# tapecleaner.net
KiCad netlist of a schematic drawn in EAGLE
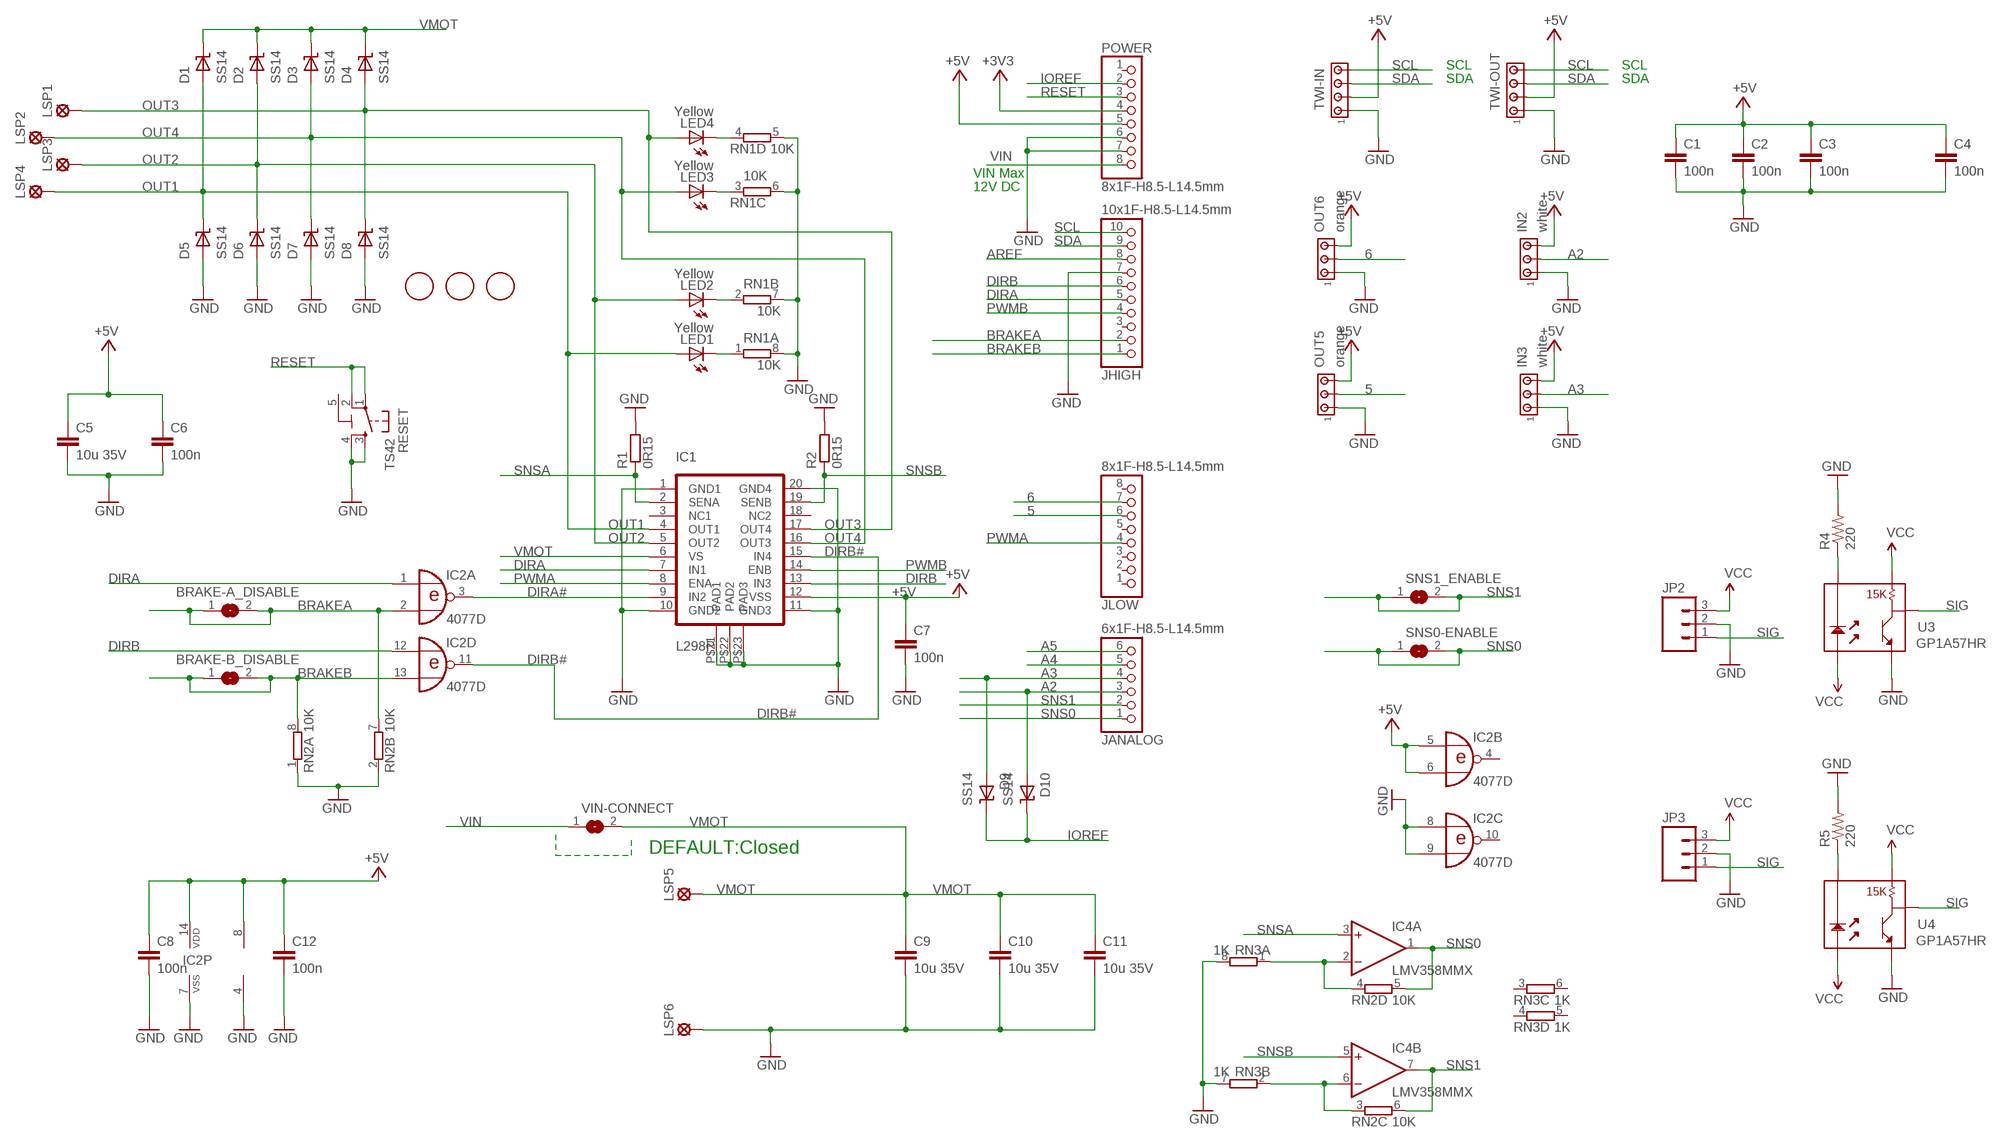
[diagram p0: schematic, sheet 1]
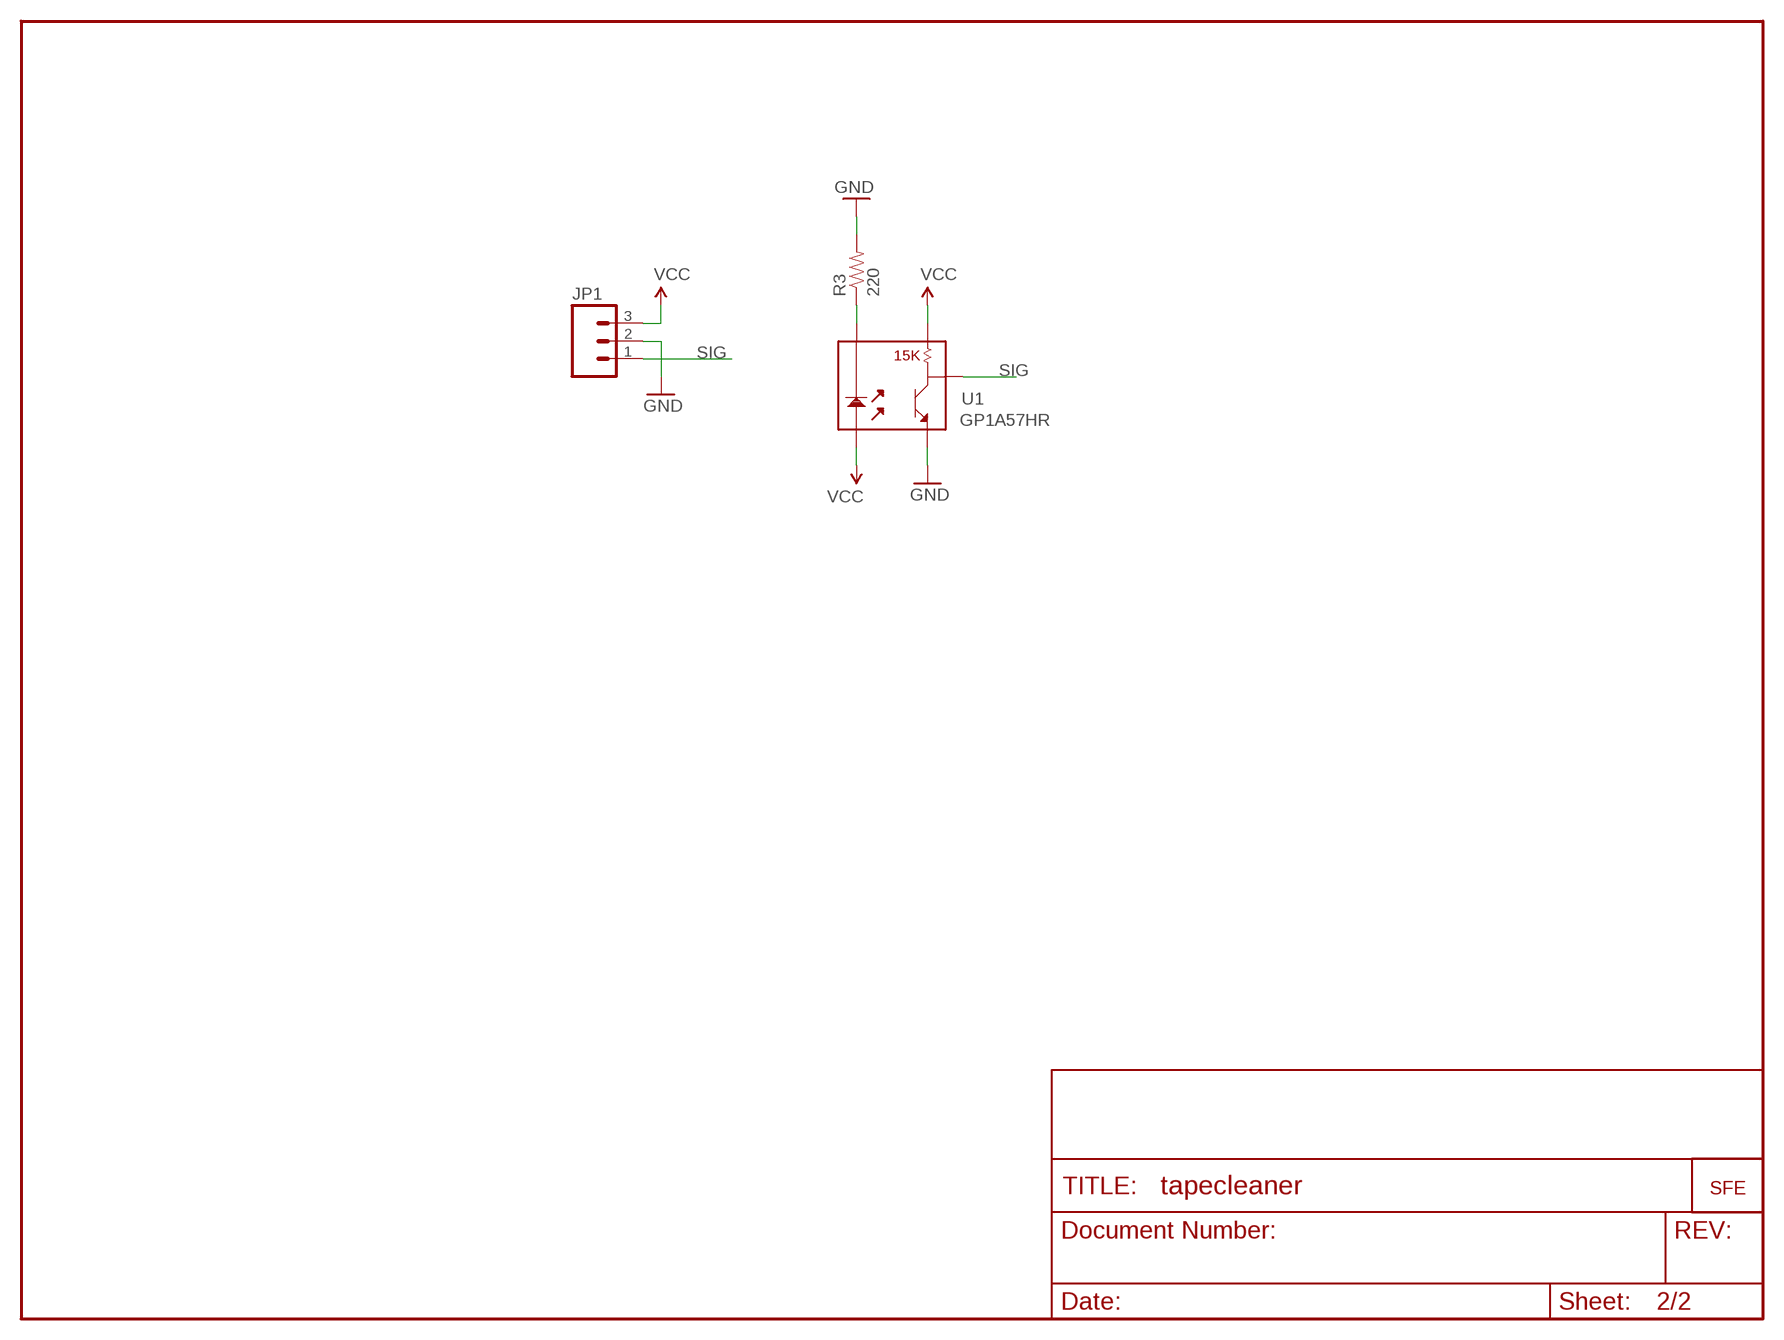
[diagram p1: schematic, sheet 2]

(export (version "E")
  (design (tool "Eeschema 10.0.6"))
  (components
    (comp (ref "JP1")
      (value "M03PTH")
      (footprint "eagle-import:1X03")
      (libsource (lib "eagle-import") (part "M03PTH"))
    )
    (comp (ref "R3")
      (value "220")
      (footprint "eagle-import:AXIAL-0.3")
      (libsource (lib "eagle-import") (part "RESISTORPTH1"))
    )
    (comp (ref "U1")
      (value "GP1A57HR")
      (footprint "eagle-import:GP1A57HR")
      (libsource (lib "eagle-import") (part "GP1A57HR"))
    )
    (comp (ref "U2")
      (value "LOGO-SFESK")
      (footprint "eagle-import:SFE-LOGO-FLAME")
      (libsource (lib "eagle-import") (part "LOGO-SFESK"))
    )
    (comp (ref "BRAKE-A_DISABLE")
      (value "SJ")
      (footprint "eagle-import:SJ")
      (libsource (lib "eagle-import") (part "SJ"))
    )
    (comp (ref "BRAKE-B_DISABLE")
      (value "SJ")
      (footprint "eagle-import:SJ")
      (libsource (lib "eagle-import") (part "SJ"))
    )
    (comp (ref "C1")
      (value "100n")
      (footprint "eagle-import:C0603-ROUND")
      (libsource (lib "eagle-import") (part "C-EUC0603"))
    )
    (comp (ref "C2")
      (value "100n")
      (footprint "eagle-import:C0603-ROUND")
      (libsource (lib "eagle-import") (part "C-EUC0603"))
    )
    (comp (ref "C3")
      (value "100n")
      (footprint "eagle-import:C0603-ROUND")
      (libsource (lib "eagle-import") (part "C-EUC0603"))
    )
    (comp (ref "C4")
      (value "100n")
      (footprint "eagle-import:C0603-ROUND")
      (libsource (lib "eagle-import") (part "C-EUC0603"))
    )
    (comp (ref "C5")
      (value "10u 35V")
      (footprint "eagle-import:C1210")
      (libsource (lib "eagle-import") (part "C-EUC1210"))
    )
    (comp (ref "C6")
      (value "100n")
      (footprint "eagle-import:C0603-ROUND")
      (libsource (lib "eagle-import") (part "C-EUC0603"))
    )
    (comp (ref "C7")
      (value "100n")
      (footprint "eagle-import:C0603-ROUND")
      (libsource (lib "eagle-import") (part "C-EUC0603"))
    )
    (comp (ref "C8")
      (value "100n")
      (footprint "eagle-import:C0603-ROUND")
      (libsource (lib "eagle-import") (part "C-EUC0603"))
    )
    (comp (ref "C9")
      (value "10u 35V")
      (footprint "eagle-import:C1210")
      (libsource (lib "eagle-import") (part "C-EUC1210"))
    )
    (comp (ref "C10")
      (value "10u 35V")
      (footprint "eagle-import:C1210")
      (libsource (lib "eagle-import") (part "C-EUC1210"))
    )
    (comp (ref "C11")
      (value "10u 35V")
      (footprint "eagle-import:C1210")
      (libsource (lib "eagle-import") (part "C-EUC1210"))
    )
    (comp (ref "C12")
      (value "100n")
      (footprint "eagle-import:C0603-ROUND")
      (libsource (lib "eagle-import") (part "C-EUC0603"))
    )
    (comp (ref "D1")
      (value "SS14")
      (footprint "eagle-import:SMA")
      (libsource (lib "eagle-import") (part "SS14"))
    )
    (comp (ref "D2")
      (value "SS14")
      (footprint "eagle-import:SMA")
      (libsource (lib "eagle-import") (part "SS14"))
    )
    (comp (ref "D3")
      (value "SS14")
      (footprint "eagle-import:SMA")
      (libsource (lib "eagle-import") (part "SS14"))
    )
    (comp (ref "D4")
      (value "SS14")
      (footprint "eagle-import:SMA")
      (libsource (lib "eagle-import") (part "SS14"))
    )
    (comp (ref "D5")
      (value "SS14")
      (footprint "eagle-import:SMA")
      (libsource (lib "eagle-import") (part "SS14"))
    )
    (comp (ref "D6")
      (value "SS14")
      (footprint "eagle-import:SMA")
      (libsource (lib "eagle-import") (part "SS14"))
    )
    (comp (ref "D7")
      (value "SS14")
      (footprint "eagle-import:SMA")
      (libsource (lib "eagle-import") (part "SS14"))
    )
    (comp (ref "D8")
      (value "SS14")
      (footprint "eagle-import:SMA")
      (libsource (lib "eagle-import") (part "SS14"))
    )
    (comp (ref "D9")
      (value "SS14")
      (footprint "eagle-import:SMA")
      (libsource (lib "eagle-import") (part "SS14"))
    )
    (comp (ref "D10")
      (value "SS14")
      (footprint "eagle-import:SMA")
      (libsource (lib "eagle-import") (part "SS14"))
    )
    (comp (ref "FID1")
      (value "FIDUCIALMOUNT")
      (footprint "eagle-import:FIDUCIA-MOUNT")
      (libsource (lib "eagle-import") (part "FIDUCIALMOUNT"))
    )
    (comp (ref "FID2")
      (value "FIDUCIALMOUNT")
      (footprint "eagle-import:FIDUCIA-MOUNT")
      (libsource (lib "eagle-import") (part "FIDUCIALMOUNT"))
    )
    (comp (ref "FID3")
      (value "FIDUCIALMOUNT")
      (footprint "eagle-import:FIDUCIA-MOUNT")
      (libsource (lib "eagle-import") (part "FIDUCIALMOUNT"))
    )
    (comp (ref "IC1")
      (value "L298P")
      (footprint "eagle-import:POWER-SO20")
      (libsource (lib "eagle-import") (part "L298P"))
    )
    (comp (ref "IC2")
      (value "4077D")
      (footprint "eagle-import:SO14")
      (libsource (lib "eagle-import") (part "4077D"))
    )
    (comp (ref "IC4")
      (value "LMV358MMX")
      (footprint "eagle-import:MSOP08")
      (libsource (lib "eagle-import") (part "LMV358?MMX"))
    )
    (comp (ref "IN2")
      (value "white")
      (footprint "eagle-import:10X03MTA")
      (libsource (lib "eagle-import") (part "MTA03-100"))
    )
    (comp (ref "IN3")
      (value "white")
      (footprint "eagle-import:10X03MTA")
      (libsource (lib "eagle-import") (part "MTA03-100"))
    )
    (comp (ref "JANALOG")
      (value "6x1F-H8.5-L14.5mm")
      (footprint "eagle-import:1X06-TH")
      (libsource (lib "eagle-import") (part "PINHD-1X6TH"))
    )
    (comp (ref "JHIGH")
      (value "10x1F-H8.5-L14.5mm")
      (footprint "eagle-import:1X10-TH")
      (libsource (lib "eagle-import") (part "PINHD-1X10TH"))
    )
    (comp (ref "JLOW")
      (value "8x1F-H8.5-L14.5mm")
      (footprint "eagle-import:1X08-TH")
      (libsource (lib "eagle-import") (part "PINHD-1X8TH"))
    )
    (comp (ref "JP2")
      (value "M03PTH")
      (footprint "eagle-import:1X03")
      (libsource (lib "eagle-import") (part "M03PTH"))
    )
    (comp (ref "JP3")
      (value "M03PTH")
      (footprint "eagle-import:1X03")
      (libsource (lib "eagle-import") (part "M03PTH"))
    )
    (comp (ref "LED1")
      (value "Yellow")
      (footprint "eagle-import:CHIPLED_0805")
      (libsource (lib "eagle-import") (part "LEDCHIPLED_0805"))
    )
    (comp (ref "LED2")
      (value "Yellow")
      (footprint "eagle-import:CHIPLED_0805")
      (libsource (lib "eagle-import") (part "LEDCHIPLED_0805"))
    )
    (comp (ref "LED3")
      (value "Yellow")
      (footprint "eagle-import:CHIPLED_0805")
      (libsource (lib "eagle-import") (part "LEDCHIPLED_0805"))
    )
    (comp (ref "LED4")
      (value "Yellow")
      (footprint "eagle-import:CHIPLED_0805")
      (libsource (lib "eagle-import") (part "LEDCHIPLED_0805"))
    )
    (comp (ref "LSP1")
      (value "LSP13")
      (footprint "eagle-import:LSP13")
      (libsource (lib "eagle-import") (part "LSP13"))
    )
    (comp (ref "LSP2")
      (value "LSP13")
      (footprint "eagle-import:LSP13")
      (libsource (lib "eagle-import") (part "LSP13"))
    )
    (comp (ref "LSP3")
      (value "LSP13")
      (footprint "eagle-import:LSP13")
      (libsource (lib "eagle-import") (part "LSP13"))
    )
    (comp (ref "LSP4")
      (value "LSP13")
      (footprint "eagle-import:LSP13")
      (libsource (lib "eagle-import") (part "LSP13"))
    )
    (comp (ref "LSP5")
      (value "LSP13")
      (footprint "eagle-import:LSP13")
      (libsource (lib "eagle-import") (part "LSP13"))
    )
    (comp (ref "LSP6")
      (value "LSP13")
      (footprint "eagle-import:LSP13")
      (libsource (lib "eagle-import") (part "LSP13"))
    )
    (comp (ref "OUT5")
      (value "orange")
      (footprint "eagle-import:10X03MTA")
      (libsource (lib "eagle-import") (part "MTA03-100"))
    )
    (comp (ref "OUT6")
      (value "orange")
      (footprint "eagle-import:10X03MTA")
      (libsource (lib "eagle-import") (part "MTA03-100"))
    )
    (comp (ref "POWER")
      (value "8x1F-H8.5-L14.5mm")
      (footprint "eagle-import:1X08-TH")
      (libsource (lib "eagle-import") (part "PINHD-1X8TH"))
    )
    (comp (ref "R1")
      (value "0R15")
      (footprint "eagle-import:R1206")
      (libsource (lib "eagle-import") (part "R-EU_R1206"))
    )
    (comp (ref "R2")
      (value "0R15")
      (footprint "eagle-import:R1206")
      (libsource (lib "eagle-import") (part "R-EU_R1206"))
    )
    (comp (ref "R4")
      (value "220")
      (footprint "eagle-import:AXIAL-0.3")
      (libsource (lib "eagle-import") (part "RESISTORPTH1"))
    )
    (comp (ref "R5")
      (value "220")
      (footprint "eagle-import:AXIAL-0.3")
      (libsource (lib "eagle-import") (part "RESISTORPTH1"))
    )
    (comp (ref "RESET")
      (value "TS42")
      (footprint "eagle-import:TS42")
      (libsource (lib "eagle-import") (part "TS42"))
    )
    (comp (ref "RN1")
      (value "10K")
      (footprint "eagle-import:CAY16")
      (libsource (lib "eagle-import") (part "4R-NCAY16"))
    )
    (comp (ref "RN2")
      (value "10K")
      (footprint "eagle-import:CAY16")
      (libsource (lib "eagle-import") (part "4R-NCAY16"))
    )
    (comp (ref "RN3")
      (value "1K")
      (footprint "eagle-import:CAY16")
      (libsource (lib "eagle-import") (part "4R-NCAY16"))
    )
    (comp (ref "SNS0-ENABLE")
      (value "SJ")
      (footprint "eagle-import:SJ")
      (libsource (lib "eagle-import") (part "SJ"))
    )
    (comp (ref "SNS1_ENABLE")
      (value "SJ")
      (footprint "eagle-import:SJ")
      (libsource (lib "eagle-import") (part "SJ"))
    )
    (comp (ref "TWI-IN")
      (value "MTA04-100")
      (footprint "eagle-import:10X04MTA")
      (libsource (lib "eagle-import") (part "MTA04-100"))
    )
    (comp (ref "TWI-OUT")
      (value "MTA04-100")
      (footprint "eagle-import:10X04MTA")
      (libsource (lib "eagle-import") (part "MTA04-100"))
    )
    (comp (ref "U3")
      (value "GP1A57HR")
      (footprint "eagle-import:GP1A57HR")
      (libsource (lib "eagle-import") (part "GP1A57HR"))
    )
    (comp (ref "U4")
      (value "GP1A57HR")
      (footprint "eagle-import:GP1A57HR")
      (libsource (lib "eagle-import") (part "GP1A57HR"))
    )
    (comp (ref "VIN-CONNECT")
      (value "SJ")
      (footprint "eagle-import:SJ")
      (libsource (lib "eagle-import") (part "SJ"))
    )
  )
  (nets
    (net (code "1") (name "+3V3") (class "Default")
      (node (ref "POWER") (pin "4") (pinfunction "4_4") (pintype "passive"))
    )
    (net (code "2") (name "+5V") (class "Default")
      (node (ref "C1") (pin "1") (pinfunction "1_1") (pintype "passive"))
      (node (ref "C12") (pin "1") (pinfunction "1_1") (pintype "passive"))
      (node (ref "C2") (pin "1") (pinfunction "1_1") (pintype "passive"))
      (node (ref "C3") (pin "1") (pinfunction "1_1") (pintype "passive"))
      (node (ref "C4") (pin "1") (pinfunction "1_1") (pintype "passive"))
      (node (ref "C5") (pin "1") (pinfunction "1_1") (pintype "passive"))
      (node (ref "C6") (pin "1") (pinfunction "1_1") (pintype "passive"))
      (node (ref "C7") (pin "1") (pinfunction "1_1") (pintype "passive"))
      (node (ref "C8") (pin "1") (pinfunction "1_1") (pintype "passive"))
      (node (ref "IC1") (pin "P$12") (pinfunction "VSS_P$12") (pintype "power_in"))
      (node (ref "IC2") (pin "14") (pinfunction "VDD_14") (pintype "power_in"))
      (node (ref "IC2") (pin "5") (pinfunction "I0_5") (pintype "input"))
      (node (ref "IC2") (pin "6") (pinfunction "I1_6") (pintype "input"))
      (node (ref "IC4") (pin "8") (pinfunction "V+_8") (pintype "power_in"))
      (node (ref "IN2") (pin "3") (pinfunction "3_3") (pintype "passive"))
      (node (ref "IN3") (pin "3") (pinfunction "3_3") (pintype "passive"))
      (node (ref "OUT5") (pin "3") (pinfunction "3_3") (pintype "passive"))
      (node (ref "OUT6") (pin "3") (pinfunction "3_3") (pintype "passive"))
      (node (ref "POWER") (pin "5") (pinfunction "5_5") (pintype "passive"))
      (node (ref "TWI-IN") (pin "2") (pinfunction "2_2") (pintype "passive"))
      (node (ref "TWI-OUT") (pin "2") (pinfunction "2_2") (pintype "passive"))
    )
    (net (code "3") (name "5") (class "Default")
      (node (ref "JLOW") (pin "6") (pinfunction "6_6") (pintype "passive"))
      (node (ref "OUT5") (pin "2") (pinfunction "2_2") (pintype "passive"))
    )
    (net (code "4") (name "5-GND") (class "Default")
      (node (ref "RESET") (pin "5") (pinfunction "5-GND_5") (pintype "power_in"))
    )
    (net (code "5") (name "6") (class "Default")
      (node (ref "JLOW") (pin "7") (pinfunction "7_7") (pintype "passive"))
      (node (ref "OUT6") (pin "2") (pinfunction "2_2") (pintype "passive"))
    )
    (net (code "6") (name "A2") (class "Default")
      (node (ref "D10") (pin "P$2") (pinfunction "A_P$2") (pintype "bidirectional"))
      (node (ref "IN2") (pin "2") (pinfunction "2_2") (pintype "passive"))
      (node (ref "JANALOG") (pin "3") (pinfunction "3_3") (pintype "passive"))
    )
    (net (code "7") (name "A3") (class "Default")
      (node (ref "D9") (pin "P$2") (pinfunction "A_P$2") (pintype "bidirectional"))
      (node (ref "IN3") (pin "2") (pinfunction "2_2") (pintype "passive"))
      (node (ref "JANALOG") (pin "4") (pinfunction "4_4") (pintype "passive"))
    )
    (net (code "8") (name "A4") (class "Default")
      (node (ref "JANALOG") (pin "5") (pinfunction "5_5") (pintype "passive"))
    )
    (net (code "9") (name "A5") (class "Default")
      (node (ref "JANALOG") (pin "6") (pinfunction "6_6") (pintype "passive"))
    )
    (net (code "10") (name "AREF") (class "Default")
      (node (ref "JHIGH") (pin "8") (pinfunction "8_8") (pintype "passive"))
    )
    (net (code "11") (name "BRAKEA") (class "Default")
      (node (ref "BRAKE-A_DISABLE") (pin "1") (pinfunction "1_1") (pintype "passive"))
      (node (ref "BRAKE-A_DISABLE") (pin "2") (pinfunction "2_2") (pintype "passive"))
      (node (ref "IC2") (pin "2") (pinfunction "I1_2") (pintype "input"))
      (node (ref "JHIGH") (pin "2") (pinfunction "2_2") (pintype "passive"))
      (node (ref "RN2") (pin "7") (pinfunction "2_7") (pintype "passive"))
    )
    (net (code "12") (name "BRAKEB") (class "Default")
      (node (ref "BRAKE-B_DISABLE") (pin "1") (pinfunction "1_1") (pintype "passive"))
      (node (ref "BRAKE-B_DISABLE") (pin "2") (pinfunction "2_2") (pintype "passive"))
      (node (ref "IC2") (pin "13") (pinfunction "I1_13") (pintype "input"))
      (node (ref "JHIGH") (pin "1") (pinfunction "1_1") (pintype "passive"))
      (node (ref "RN2") (pin "8") (pinfunction "2_8") (pintype "passive"))
    )
    (net (code "13") (name "DIRA") (class "Default")
      (node (ref "IC1") (pin "P$7") (pinfunction "IN1_P$7") (pintype "input"))
      (node (ref "IC2") (pin "1") (pinfunction "I0_1") (pintype "input"))
      (node (ref "JHIGH") (pin "5") (pinfunction "5_5") (pintype "passive"))
    )
    (net (code "14") (name "DIRA#") (class "Default")
      (node (ref "IC1") (pin "P$9") (pinfunction "IN2_P$9") (pintype "input"))
      (node (ref "IC2") (pin "3") (pinfunction "O_3") (pintype "output"))
    )
    (net (code "15") (name "DIRB") (class "Default")
      (node (ref "IC1") (pin "P$13") (pinfunction "IN3_P$13") (pintype "input"))
      (node (ref "IC2") (pin "12") (pinfunction "I0_12") (pintype "input"))
      (node (ref "JHIGH") (pin "6") (pinfunction "6_6") (pintype "passive"))
    )
    (net (code "16") (name "DIRB#") (class "Default")
      (node (ref "IC1") (pin "P$15") (pinfunction "IN4_P$15") (pintype "input"))
      (node (ref "IC2") (pin "11") (pinfunction "O_11") (pintype "output"))
    )
    (net (code "17") (name "GND") (class "Default")
      (node (ref "C1") (pin "2") (pinfunction "2_2") (pintype "passive"))
      (node (ref "C10") (pin "2") (pinfunction "2_2") (pintype "passive"))
      (node (ref "C11") (pin "2") (pinfunction "2_2") (pintype "passive"))
      (node (ref "C12") (pin "2") (pinfunction "2_2") (pintype "passive"))
      (node (ref "C2") (pin "2") (pinfunction "2_2") (pintype "passive"))
      (node (ref "C3") (pin "2") (pinfunction "2_2") (pintype "passive"))
      (node (ref "C4") (pin "2") (pinfunction "2_2") (pintype "passive"))
      (node (ref "C5") (pin "2") (pinfunction "2_2") (pintype "passive"))
      (node (ref "C6") (pin "2") (pinfunction "2_2") (pintype "passive"))
      (node (ref "C7") (pin "2") (pinfunction "2_2") (pintype "passive"))
      (node (ref "C8") (pin "2") (pinfunction "2_2") (pintype "passive"))
      (node (ref "C9") (pin "2") (pinfunction "2_2") (pintype "passive"))
      (node (ref "D5") (pin "P$2") (pinfunction "A_P$2") (pintype "bidirectional"))
      (node (ref "D6") (pin "P$2") (pinfunction "A_P$2") (pintype "bidirectional"))
      (node (ref "D7") (pin "P$2") (pinfunction "A_P$2") (pintype "bidirectional"))
      (node (ref "D8") (pin "P$2") (pinfunction "A_P$2") (pintype "bidirectional"))
      (node (ref "IC1") (pin "P$1") (pinfunction "GND1_P$1") (pintype "power_in"))
      (node (ref "IC1") (pin "P$10") (pinfunction "GND2_P$10") (pintype "power_in"))
      (node (ref "IC1") (pin "P$11") (pinfunction "GND3_P$11") (pintype "power_in"))
      (node (ref "IC1") (pin "P$20") (pinfunction "GND4_P$20") (pintype "power_in"))
      (node (ref "IC1") (pin "P$21") (pinfunction "PAD1_P$21") (pintype "passive"))
      (node (ref "IC1") (pin "P$22") (pinfunction "PAD2_P$22") (pintype "passive"))
      (node (ref "IC1") (pin "P$23") (pinfunction "PAD3_P$23") (pintype "passive"))
      (node (ref "IC2") (pin "7") (pinfunction "VSS_7") (pintype "power_in"))
      (node (ref "IC2") (pin "8") (pinfunction "I0_8") (pintype "input"))
      (node (ref "IC2") (pin "9") (pinfunction "I1_9") (pintype "input"))
      (node (ref "IC4") (pin "4") (pinfunction "V-_4") (pintype "power_in"))
      (node (ref "IN2") (pin "1") (pinfunction "1_1") (pintype "passive"))
      (node (ref "IN3") (pin "1") (pinfunction "1_1") (pintype "passive"))
      (node (ref "JHIGH") (pin "7") (pinfunction "7_7") (pintype "passive"))
      (node (ref "JP1") (pin "2") (pinfunction "2_2") (pintype "passive"))
      (node (ref "JP2") (pin "2") (pinfunction "2_2") (pintype "passive"))
      (node (ref "JP3") (pin "2") (pinfunction "2_2") (pintype "passive"))
      (node (ref "LSP6") (pin "MP") (pinfunction "MP_MP") (pintype "passive"))
      (node (ref "OUT5") (pin "1") (pinfunction "1_1") (pintype "passive"))
      (node (ref "OUT6") (pin "1") (pinfunction "1_1") (pintype "passive"))
      (node (ref "POWER") (pin "6") (pinfunction "6_6") (pintype "passive"))
      (node (ref "POWER") (pin "7") (pinfunction "7_7") (pintype "passive"))
      (node (ref "R1") (pin "2") (pinfunction "2_2") (pintype "passive"))
      (node (ref "R2") (pin "2") (pinfunction "2_2") (pintype "passive"))
      (node (ref "R3") (pin "P$2") (pinfunction "2_P$2") (pintype "passive"))
      (node (ref "R4") (pin "P$2") (pinfunction "2_P$2") (pintype "passive"))
      (node (ref "R5") (pin "P$2") (pinfunction "2_P$2") (pintype "passive"))
      (node (ref "RESET") (pin "3") (pinfunction "3_3") (pintype "passive"))
      (node (ref "RESET") (pin "4") (pinfunction "4_4") (pintype "passive"))
      (node (ref "RN1") (pin "5") (pinfunction "2_5") (pintype "passive"))
      (node (ref "RN1") (pin "6") (pinfunction "2_6") (pintype "passive"))
      (node (ref "RN1") (pin "7") (pinfunction "2_7") (pintype "passive"))
      (node (ref "RN1") (pin "8") (pinfunction "2_8") (pintype "passive"))
      (node (ref "RN2") (pin "1") (pinfunction "1_1") (pintype "passive"))
      (node (ref "RN2") (pin "2") (pinfunction "1_2") (pintype "passive"))
      (node (ref "RN3") (pin "7") (pinfunction "2_7") (pintype "passive"))
      (node (ref "RN3") (pin "8") (pinfunction "2_8") (pintype "passive"))
      (node (ref "TWI-IN") (pin "1") (pinfunction "1_1") (pintype "passive"))
      (node (ref "TWI-OUT") (pin "1") (pinfunction "1_1") (pintype "passive"))
      (node (ref "U1") (pin "5") (pinfunction "5_5") (pintype "bidirectional"))
      (node (ref "U3") (pin "5") (pinfunction "5_5") (pintype "bidirectional"))
      (node (ref "U4") (pin "5") (pinfunction "5_5") (pintype "bidirectional"))
    )
    (net (code "18") (name "IOREF") (class "Default")
      (node (ref "D10") (pin "P$1") (pinfunction "K_P$1") (pintype "bidirectional"))
      (node (ref "D9") (pin "P$1") (pinfunction "K_P$1") (pintype "bidirectional"))
      (node (ref "POWER") (pin "2") (pinfunction "2_2") (pintype "passive"))
    )
    (net (code "19") (name "Net-(IC4A--IN)") (class "Default")
      (node (ref "IC4") (pin "2") (pinfunction "-IN_2") (pintype "input"))
      (node (ref "RN2") (pin "4") (pinfunction "1_4") (pintype "passive"))
      (node (ref "RN3") (pin "1") (pinfunction "1_1") (pintype "passive"))
    )
    (net (code "20") (name "Net-(IC4B--IN)") (class "Default")
      (node (ref "IC4") (pin "6") (pinfunction "-IN_6") (pintype "input"))
      (node (ref "RN2") (pin "3") (pinfunction "1_3") (pintype "passive"))
      (node (ref "RN3") (pin "2") (pinfunction "1_2") (pintype "passive"))
    )
    (net (code "21") (name "Net-(LED1-PadC)") (class "Default")
      (node (ref "LED1") (pin "C") (pinfunction "C_C") (pintype "passive"))
      (node (ref "RN1") (pin "1") (pinfunction "1_1") (pintype "passive"))
    )
    (net (code "22") (name "Net-(R3-1)") (class "Default")
      (node (ref "R3") (pin "P$1") (pinfunction "1_P$1") (pintype "passive"))
      (node (ref "U1") (pin "2") (pinfunction "2_2") (pintype "bidirectional"))
    )
    (net (code "23") (name "Net-(R4-1)") (class "Default")
      (node (ref "R4") (pin "P$1") (pinfunction "1_P$1") (pintype "passive"))
      (node (ref "U3") (pin "2") (pinfunction "2_2") (pintype "bidirectional"))
    )
    (net (code "24") (name "Net-(R5-1)") (class "Default")
      (node (ref "R5") (pin "P$1") (pinfunction "1_P$1") (pintype "passive"))
      (node (ref "U4") (pin "2") (pinfunction "2_2") (pintype "bidirectional"))
    )
    (net (code "25") (name "Net-(RN1B-1)") (class "Default")
      (node (ref "LED2") (pin "C") (pinfunction "C_C") (pintype "passive"))
      (node (ref "RN1") (pin "2") (pinfunction "1_2") (pintype "passive"))
    )
    (net (code "26") (name "Net-(RN1C-1)") (class "Default")
      (node (ref "LED3") (pin "C") (pinfunction "C_C") (pintype "passive"))
      (node (ref "RN1") (pin "3") (pinfunction "1_3") (pintype "passive"))
    )
    (net (code "27") (name "Net-(RN1D-1)") (class "Default")
      (node (ref "LED4") (pin "C") (pinfunction "C_C") (pintype "passive"))
      (node (ref "RN1") (pin "4") (pinfunction "1_4") (pintype "passive"))
    )
    (net (code "28") (name "OUT1") (class "Default")
      (node (ref "D1") (pin "P$2") (pinfunction "A_P$2") (pintype "bidirectional"))
      (node (ref "D5") (pin "P$1") (pinfunction "K_P$1") (pintype "bidirectional"))
      (node (ref "IC1") (pin "P$4") (pinfunction "OUT1_P$4") (pintype "output"))
      (node (ref "LED1") (pin "A") (pinfunction "A_A") (pintype "passive"))
      (node (ref "LSP4") (pin "MP") (pinfunction "MP_MP") (pintype "passive"))
    )
    (net (code "29") (name "OUT2") (class "Default")
      (node (ref "D2") (pin "P$2") (pinfunction "A_P$2") (pintype "bidirectional"))
      (node (ref "D6") (pin "P$1") (pinfunction "K_P$1") (pintype "bidirectional"))
      (node (ref "IC1") (pin "P$5") (pinfunction "OUT2_P$5") (pintype "output"))
      (node (ref "LED2") (pin "A") (pinfunction "A_A") (pintype "passive"))
      (node (ref "LSP3") (pin "MP") (pinfunction "MP_MP") (pintype "passive"))
    )
    (net (code "30") (name "OUT3") (class "Default")
      (node (ref "D4") (pin "P$2") (pinfunction "A_P$2") (pintype "bidirectional"))
      (node (ref "D8") (pin "P$1") (pinfunction "K_P$1") (pintype "bidirectional"))
      (node (ref "IC1") (pin "P$17") (pinfunction "OUT4_P$17") (pintype "output"))
      (node (ref "LED4") (pin "A") (pinfunction "A_A") (pintype "passive"))
      (node (ref "LSP1") (pin "MP") (pinfunction "MP_MP") (pintype "passive"))
    )
    (net (code "31") (name "OUT4") (class "Default")
      (node (ref "D3") (pin "P$2") (pinfunction "A_P$2") (pintype "bidirectional"))
      (node (ref "D7") (pin "P$1") (pinfunction "K_P$1") (pintype "bidirectional"))
      (node (ref "IC1") (pin "P$16") (pinfunction "OUT3_P$16") (pintype "output"))
      (node (ref "LED3") (pin "A") (pinfunction "A_A") (pintype "passive"))
      (node (ref "LSP2") (pin "MP") (pinfunction "MP_MP") (pintype "passive"))
    )
    (net (code "32") (name "PWMA") (class "Default")
      (node (ref "IC1") (pin "P$8") (pinfunction "ENA_P$8") (pintype "input"))
      (node (ref "JLOW") (pin "4") (pinfunction "4_4") (pintype "passive"))
    )
    (net (code "33") (name "PWMB") (class "Default")
      (node (ref "IC1") (pin "P$14") (pinfunction "ENB_P$14") (pintype "input"))
      (node (ref "JHIGH") (pin "4") (pinfunction "4_4") (pintype "passive"))
    )
    (net (code "34") (name "RESET") (class "Default")
      (node (ref "POWER") (pin "3") (pinfunction "3_3") (pintype "passive"))
      (node (ref "RESET") (pin "1") (pinfunction "1_1") (pintype "passive"))
      (node (ref "RESET") (pin "2") (pinfunction "2_2") (pintype "passive"))
    )
    (net (code "35") (name "SCL") (class "Default")
      (node (ref "JHIGH") (pin "10") (pinfunction "10_10") (pintype "passive"))
      (node (ref "TWI-IN") (pin "4") (pinfunction "4_4") (pintype "passive"))
      (node (ref "TWI-OUT") (pin "4") (pinfunction "4_4") (pintype "passive"))
    )
    (net (code "36") (name "SDA") (class "Default")
      (node (ref "JHIGH") (pin "9") (pinfunction "9_9") (pintype "passive"))
      (node (ref "TWI-IN") (pin "3") (pinfunction "3_3") (pintype "passive"))
      (node (ref "TWI-OUT") (pin "3") (pinfunction "3_3") (pintype "passive"))
    )
    (net (code "37") (name "SIG") (class "Default")
      (node (ref "JP1") (pin "1") (pinfunction "1_1") (pintype "passive"))
      (node (ref "JP2") (pin "1") (pinfunction "1_1") (pintype "passive"))
      (node (ref "JP3") (pin "1") (pinfunction "1_1") (pintype "passive"))
      (node (ref "U1") (pin "4") (pinfunction "4_4") (pintype "bidirectional"))
      (node (ref "U3") (pin "4") (pinfunction "4_4") (pintype "bidirectional"))
      (node (ref "U4") (pin "4") (pinfunction "4_4") (pintype "bidirectional"))
    )
    (net (code "38") (name "SNS0") (class "Default")
      (node (ref "IC4") (pin "1") (pinfunction "OUT_1") (pintype "output"))
      (node (ref "JANALOG") (pin "1") (pinfunction "1_1") (pintype "passive"))
      (node (ref "RN2") (pin "5") (pinfunction "2_5") (pintype "passive"))
      (node (ref "SNS0-ENABLE") (pin "1") (pinfunction "1_1") (pintype "passive"))
      (node (ref "SNS0-ENABLE") (pin "2") (pinfunction "2_2") (pintype "passive"))
    )
    (net (code "39") (name "SNS1") (class "Default")
      (node (ref "IC4") (pin "7") (pinfunction "OUT_7") (pintype "output"))
      (node (ref "JANALOG") (pin "2") (pinfunction "2_2") (pintype "passive"))
      (node (ref "RN2") (pin "6") (pinfunction "2_6") (pintype "passive"))
      (node (ref "SNS1_ENABLE") (pin "1") (pinfunction "1_1") (pintype "passive"))
      (node (ref "SNS1_ENABLE") (pin "2") (pinfunction "2_2") (pintype "passive"))
    )
    (net (code "40") (name "SNSA") (class "Default")
      (node (ref "IC1") (pin "P$2") (pinfunction "SENA_P$2") (pintype "input"))
      (node (ref "IC4") (pin "3") (pinfunction "+IN_3") (pintype "input"))
      (node (ref "R1") (pin "1") (pinfunction "1_1") (pintype "passive"))
    )
    (net (code "41") (name "SNSB") (class "Default")
      (node (ref "IC1") (pin "P$19") (pinfunction "SENB_P$19") (pintype "input"))
      (node (ref "IC4") (pin "5") (pinfunction "+IN_5") (pintype "input"))
      (node (ref "R2") (pin "1") (pinfunction "1_1") (pintype "passive"))
    )
    (net (code "42") (name "VCC") (class "Default")
      (node (ref "JP1") (pin "3") (pinfunction "3_3") (pintype "passive"))
      (node (ref "JP2") (pin "3") (pinfunction "3_3") (pintype "passive"))
      (node (ref "JP3") (pin "3") (pinfunction "3_3") (pintype "passive"))
      (node (ref "U1") (pin "1") (pinfunction "1_1") (pintype "bidirectional"))
      (node (ref "U1") (pin "3") (pinfunction "3_3") (pintype "bidirectional"))
      (node (ref "U3") (pin "1") (pinfunction "1_1") (pintype "bidirectional"))
      (node (ref "U3") (pin "3") (pinfunction "3_3") (pintype "bidirectional"))
      (node (ref "U4") (pin "1") (pinfunction "1_1") (pintype "bidirectional"))
      (node (ref "U4") (pin "3") (pinfunction "3_3") (pintype "bidirectional"))
    )
    (net (code "43") (name "VIN") (class "Default")
      (node (ref "POWER") (pin "8") (pinfunction "8_8") (pintype "passive"))
      (node (ref "VIN-CONNECT") (pin "1") (pinfunction "1_1") (pintype "passive"))
    )
    (net (code "44") (name "VMOT") (class "Default")
      (node (ref "C10") (pin "1") (pinfunction "1_1") (pintype "passive"))
      (node (ref "C11") (pin "1") (pinfunction "1_1") (pintype "passive"))
      (node (ref "C9") (pin "1") (pinfunction "1_1") (pintype "passive"))
      (node (ref "D1") (pin "P$1") (pinfunction "K_P$1") (pintype "bidirectional"))
      (node (ref "D2") (pin "P$1") (pinfunction "K_P$1") (pintype "bidirectional"))
      (node (ref "D3") (pin "P$1") (pinfunction "K_P$1") (pintype "bidirectional"))
      (node (ref "D4") (pin "P$1") (pinfunction "K_P$1") (pintype "bidirectional"))
      (node (ref "IC1") (pin "P$6") (pinfunction "VS_P$6") (pintype "power_in"))
      (node (ref "LSP5") (pin "MP") (pinfunction "MP_MP") (pintype "passive"))
      (node (ref "VIN-CONNECT") (pin "2") (pinfunction "2_2") (pintype "passive"))
    )
    (net (code "45") (name "unconnected-(IC1-NC1-PadP$3)") (class "Default")
      (node (ref "IC1") (pin "P$3") (pinfunction "NC1_P$3") (pintype "no_connect"))
    )
    (net (code "46") (name "unconnected-(IC1-NC2-PadP$18)") (class "Default")
      (node (ref "IC1") (pin "P$18") (pinfunction "NC2_P$18") (pintype "no_connect"))
    )
    (net (code "47") (name "unconnected-(IC2B-O-Pad4)") (class "Default")
      (node (ref "IC2") (pin "4") (pinfunction "O_4") (pintype "output"))
    )
    (net (code "48") (name "unconnected-(IC2C-O-Pad10)") (class "Default")
      (node (ref "IC2") (pin "10") (pinfunction "O_10") (pintype "output"))
    )
    (net (code "49") (name "unconnected-(JHIGH-Pad3)") (class "Default")
      (node (ref "JHIGH") (pin "3") (pinfunction "3_3") (pintype "passive"))
    )
    (net (code "50") (name "unconnected-(JLOW-Pad1)") (class "Default")
      (node (ref "JLOW") (pin "1") (pinfunction "1_1") (pintype "passive"))
    )
    (net (code "51") (name "unconnected-(JLOW-Pad2)") (class "Default")
      (node (ref "JLOW") (pin "2") (pinfunction "2_2") (pintype "passive"))
    )
    (net (code "52") (name "unconnected-(JLOW-Pad3)") (class "Default")
      (node (ref "JLOW") (pin "3") (pinfunction "3_3") (pintype "passive"))
    )
    (net (code "53") (name "unconnected-(JLOW-Pad5)") (class "Default")
      (node (ref "JLOW") (pin "5") (pinfunction "5_5") (pintype "passive"))
    )
    (net (code "54") (name "unconnected-(JLOW-Pad8)") (class "Default")
      (node (ref "JLOW") (pin "8") (pinfunction "8_8") (pintype "passive"))
    )
    (net (code "55") (name "unconnected-(POWER-Pad1)") (class "Default")
      (node (ref "POWER") (pin "1") (pinfunction "1_1") (pintype "passive"))
    )
    (net (code "56") (name "unconnected-(RN3C-1-Pad3)") (class "Default")
      (node (ref "RN3") (pin "3") (pinfunction "1_3") (pintype "passive"))
    )
    (net (code "57") (name "unconnected-(RN3C-2-Pad6)") (class "Default")
      (node (ref "RN3") (pin "6") (pinfunction "2_6") (pintype "passive"))
    )
    (net (code "58") (name "unconnected-(RN3D-1-Pad4)") (class "Default")
      (node (ref "RN3") (pin "4") (pinfunction "1_4") (pintype "passive"))
    )
    (net (code "59") (name "unconnected-(RN3D-2-Pad5)") (class "Default")
      (node (ref "RN3") (pin "5") (pinfunction "2_5") (pintype "passive"))
    )
  )
)
